# M703X.net
KiCad netlist of a schematic drawn in EAGLE
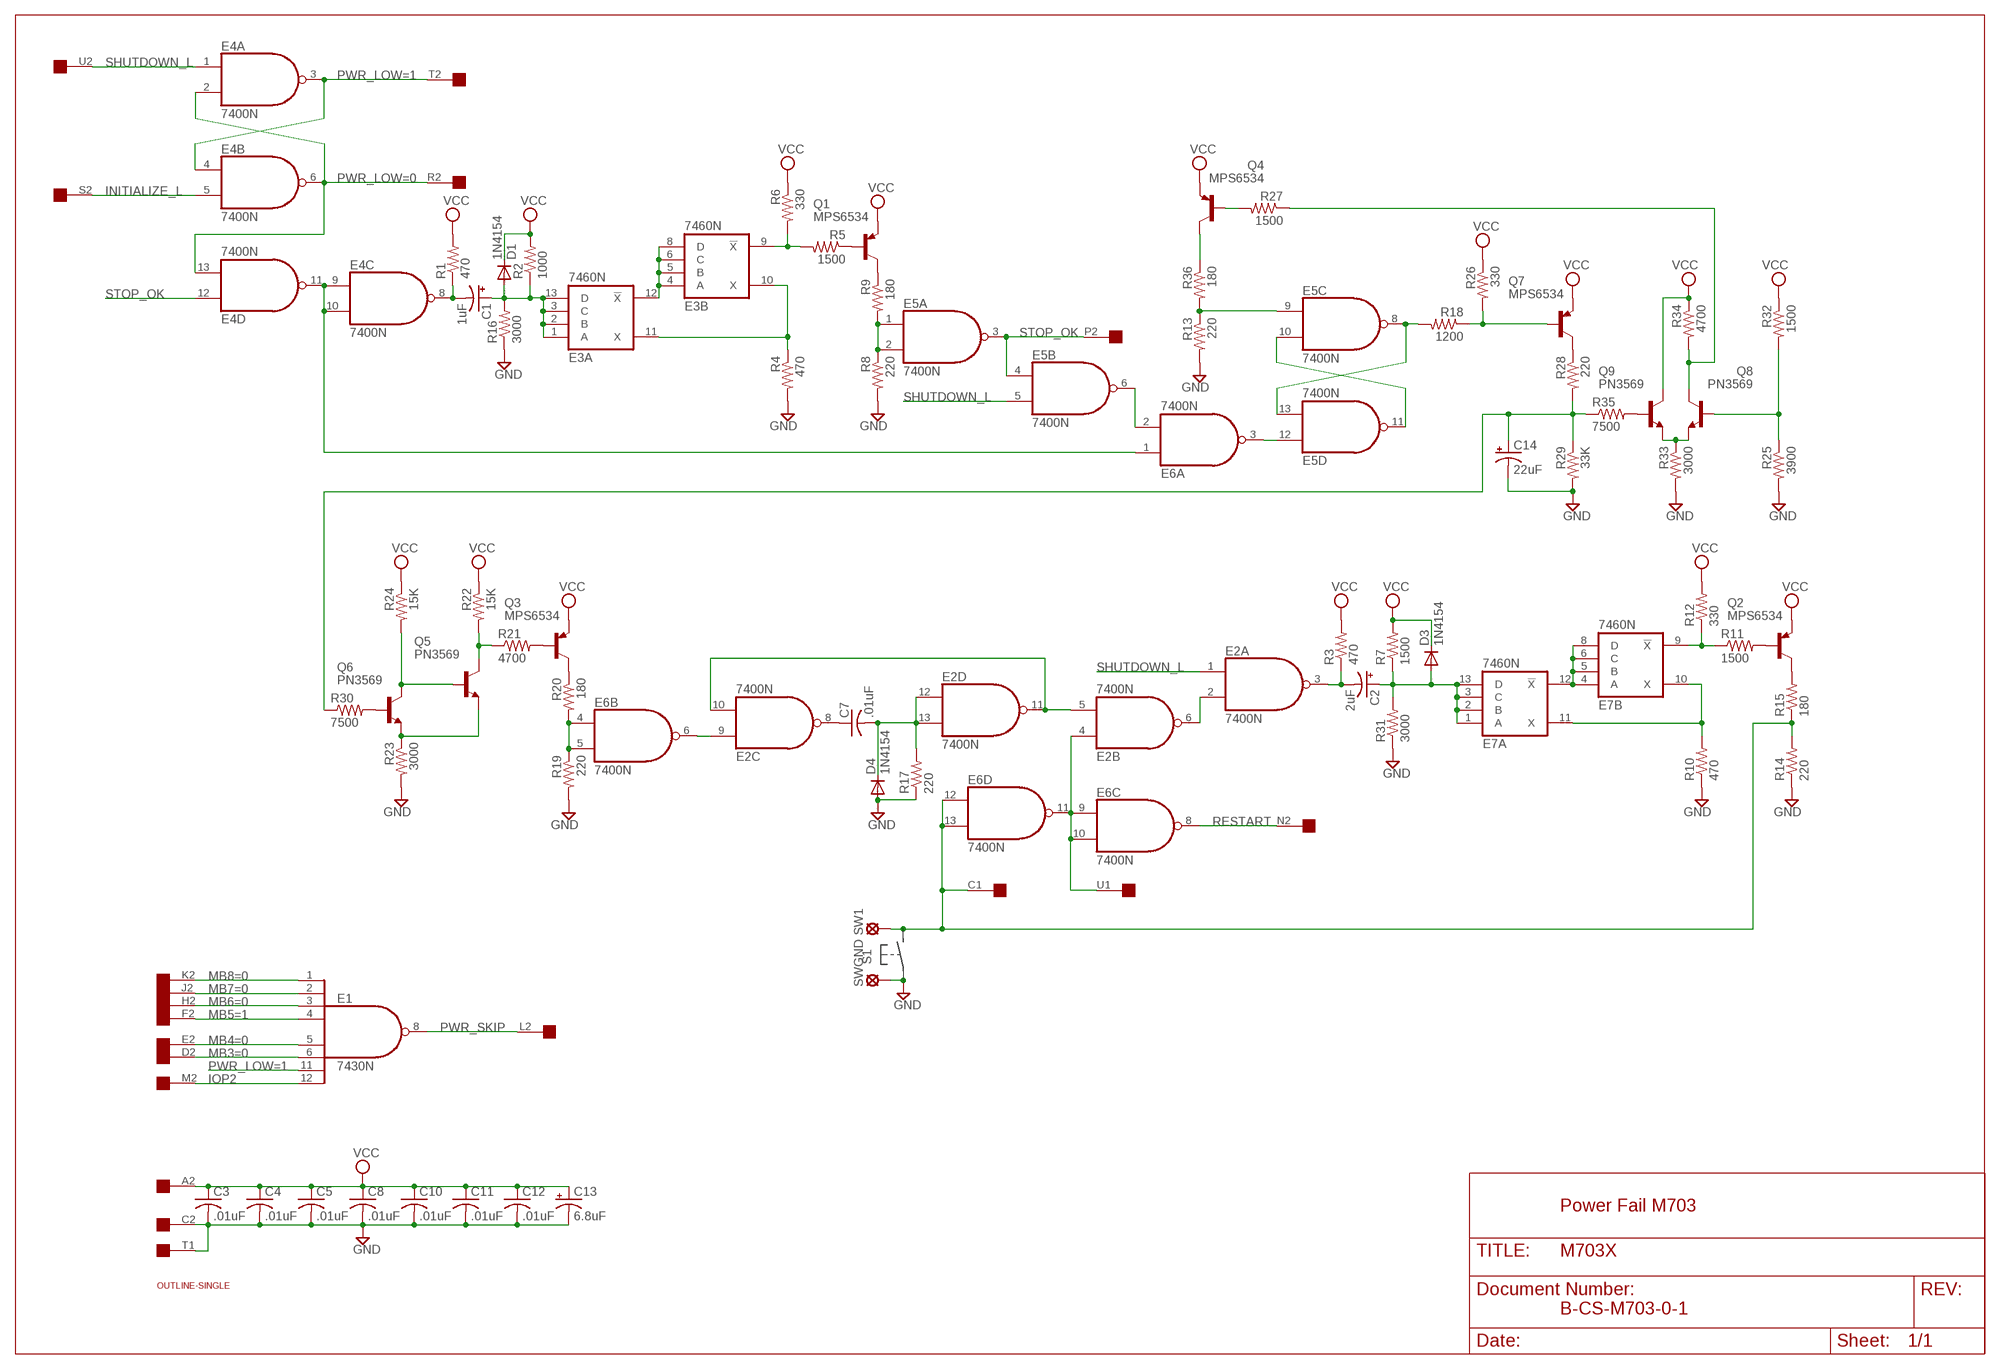
[diagram p0: schematic, sheet 1]

(export (version "E")
  (design (tool "Eeschema 10.0.6"))
  (components
    (comp (ref "C1")
      (value "1uF")
      (footprint "eagle-import:E12-4")
      (libsource (lib "eagle-import") (part "CPOL-USE12-4AXIAL"))
    )
    (comp (ref "C2")
      (value "2uF")
      (footprint "eagle-import:E12-4")
      (libsource (lib "eagle-import") (part "CPOL-USE12-4AXIAL"))
    )
    (comp (ref "C3")
      (value ".01uF")
      (footprint "eagle-import:C050-025X075")
      (libsource (lib "eagle-import") (part "C-US050-025X075"))
    )
    (comp (ref "C4")
      (value ".01uF")
      (footprint "eagle-import:C050-025X075")
      (libsource (lib "eagle-import") (part "C-US050-025X075"))
    )
    (comp (ref "C5")
      (value ".01uF")
      (footprint "eagle-import:C050-025X075")
      (libsource (lib "eagle-import") (part "C-US050-025X075"))
    )
    (comp (ref "C7")
      (value ".01uF")
      (footprint "eagle-import:C050-025X075")
      (libsource (lib "eagle-import") (part "C-US050-025X075"))
    )
    (comp (ref "C8")
      (value ".01uF")
      (footprint "eagle-import:C050-025X075")
      (libsource (lib "eagle-import") (part "C-US050-025X075"))
    )
    (comp (ref "C10")
      (value ".01uF")
      (footprint "eagle-import:C050-025X075")
      (libsource (lib "eagle-import") (part "C-US050-025X075"))
    )
    (comp (ref "C11")
      (value ".01uF")
      (footprint "eagle-import:C050-025X075")
      (libsource (lib "eagle-import") (part "C-US050-025X075"))
    )
    (comp (ref "C12")
      (value ".01uF")
      (footprint "eagle-import:C050-025X075")
      (libsource (lib "eagle-import") (part "C-US050-025X075"))
    )
    (comp (ref "C13")
      (value "6.8uF")
      (footprint "eagle-import:E15-5")
      (libsource (lib "eagle-import") (part "CPOL-USE15-5AXIAL"))
    )
    (comp (ref "C14")
      (value "22uF")
      (footprint "eagle-import:E15-5")
      (libsource (lib "eagle-import") (part "CPOL-USE15-5AXIAL"))
    )
    (comp (ref "D1")
      (value "1N4154")
      (footprint "eagle-import:DO35-10")
      (libsource (lib "eagle-import") (part "1N4148DO35-10"))
    )
    (comp (ref "D3")
      (value "1N4154")
      (footprint "eagle-import:DO35-10")
      (libsource (lib "eagle-import") (part "1N4148DO35-10"))
    )
    (comp (ref "D4")
      (value "1N4154")
      (footprint "eagle-import:DO35-10")
      (libsource (lib "eagle-import") (part "1N4148DO35-10"))
    )
    (comp (ref "E1")
      (value "7430N")
      (footprint "eagle-import:DIL14")
      (libsource (lib "eagle-import") (part "7430N"))
    )
    (comp (ref "E2")
      (value "7400N")
      (footprint "eagle-import:DIL14")
      (libsource (lib "eagle-import") (part "7400N"))
    )
    (comp (ref "E3")
      (value "7460N")
      (footprint "eagle-import:DIL14")
      (libsource (lib "eagle-import") (part "7460N"))
    )
    (comp (ref "E4")
      (value "7400N")
      (footprint "eagle-import:DIL14")
      (libsource (lib "eagle-import") (part "7400N"))
    )
    (comp (ref "E5")
      (value "7400N")
      (footprint "eagle-import:DIL14")
      (libsource (lib "eagle-import") (part "7400N"))
    )
    (comp (ref "E6")
      (value "7400N")
      (footprint "eagle-import:DIL14")
      (libsource (lib "eagle-import") (part "7400N"))
    )
    (comp (ref "E7")
      (value "7460N")
      (footprint "eagle-import:DIL14")
      (libsource (lib "eagle-import") (part "7460N"))
    )
    (comp (ref "Q1")
      (value "MPS6534")
      (footprint "eagle-import:TO39")
      (libsource (lib "eagle-import") (part "2N2904"))
    )
    (comp (ref "Q2")
      (value "MPS6534")
      (footprint "eagle-import:TO39")
      (libsource (lib "eagle-import") (part "2N2904"))
    )
    (comp (ref "Q3")
      (value "MPS6534")
      (footprint "eagle-import:TO39")
      (libsource (lib "eagle-import") (part "2N2904"))
    )
    (comp (ref "Q4")
      (value "MPS6534")
      (footprint "eagle-import:TO39")
      (libsource (lib "eagle-import") (part "2N2904"))
    )
    (comp (ref "Q5")
      (value "PN3569")
      (footprint "eagle-import:TO5")
      (libsource (lib "eagle-import") (part "2N2219"))
    )
    (comp (ref "Q6")
      (value "PN3569")
      (footprint "eagle-import:TO5")
      (libsource (lib "eagle-import") (part "2N2219"))
    )
    (comp (ref "Q7")
      (value "MPS6534")
      (footprint "eagle-import:TO39")
      (libsource (lib "eagle-import") (part "2N2904"))
    )
    (comp (ref "Q8")
      (value "PN3569")
      (footprint "eagle-import:TO5")
      (libsource (lib "eagle-import") (part "2N2219"))
    )
    (comp (ref "Q9")
      (value "PN3569")
      (footprint "eagle-import:TO5")
      (libsource (lib "eagle-import") (part "2N2219"))
    )
    (comp (ref "R1")
      (value "470")
      (footprint "eagle-import:0207_10")
      (libsource (lib "eagle-import") (part "R-US_0207/10"))
    )
    (comp (ref "R2")
      (value "1000")
      (footprint "eagle-import:0207_10")
      (libsource (lib "eagle-import") (part "R-US_0207/10"))
    )
    (comp (ref "R3")
      (value "470")
      (footprint "eagle-import:0207_10")
      (libsource (lib "eagle-import") (part "R-US_0207/10"))
    )
    (comp (ref "R4")
      (value "470")
      (footprint "eagle-import:0207_10")
      (libsource (lib "eagle-import") (part "R-US_0207/10"))
    )
    (comp (ref "R5")
      (value "1500")
      (footprint "eagle-import:0207_10")
      (libsource (lib "eagle-import") (part "R-US_0207/10"))
    )
    (comp (ref "R6")
      (value "330")
      (footprint "eagle-import:0207_10")
      (libsource (lib "eagle-import") (part "R-US_0207/10"))
    )
    (comp (ref "R7")
      (value "1500")
      (footprint "eagle-import:0207_10")
      (libsource (lib "eagle-import") (part "R-US_0207/10"))
    )
    (comp (ref "R8")
      (value "220")
      (footprint "eagle-import:0207_10")
      (libsource (lib "eagle-import") (part "R-US_0207/10"))
    )
    (comp (ref "R9")
      (value "180")
      (footprint "eagle-import:0207_10")
      (libsource (lib "eagle-import") (part "R-US_0207/10"))
    )
    (comp (ref "R10")
      (value "470")
      (footprint "eagle-import:0207_10")
      (libsource (lib "eagle-import") (part "R-US_0207/10"))
    )
    (comp (ref "R11")
      (value "1500")
      (footprint "eagle-import:0207_10")
      (libsource (lib "eagle-import") (part "R-US_0207/10"))
    )
    (comp (ref "R12")
      (value "330")
      (footprint "eagle-import:0207_10")
      (libsource (lib "eagle-import") (part "R-US_0207/10"))
    )
    (comp (ref "R13")
      (value "220")
      (footprint "eagle-import:0207_10")
      (libsource (lib "eagle-import") (part "R-US_0207/10"))
    )
    (comp (ref "R14")
      (value "220")
      (footprint "eagle-import:0207_10")
      (libsource (lib "eagle-import") (part "R-US_0207/10"))
    )
    (comp (ref "R15")
      (value "180")
      (footprint "eagle-import:0207_10")
      (libsource (lib "eagle-import") (part "R-US_0207/10"))
    )
    (comp (ref "R16")
      (value "3000")
      (footprint "eagle-import:0207_10")
      (libsource (lib "eagle-import") (part "R-US_0207/10"))
    )
    (comp (ref "R17")
      (value "220")
      (footprint "eagle-import:0207_10")
      (libsource (lib "eagle-import") (part "R-US_0207/10"))
    )
    (comp (ref "R18")
      (value "1200")
      (footprint "eagle-import:0207_10")
      (libsource (lib "eagle-import") (part "R-US_0207/10"))
    )
    (comp (ref "R19")
      (value "220")
      (footprint "eagle-import:0207_10")
      (libsource (lib "eagle-import") (part "R-US_0207/10"))
    )
    (comp (ref "R20")
      (value "180")
      (footprint "eagle-import:0207_10")
      (libsource (lib "eagle-import") (part "R-US_0207/10"))
    )
    (comp (ref "R21")
      (value "4700")
      (footprint "eagle-import:0207_10")
      (libsource (lib "eagle-import") (part "R-US_0207/10"))
    )
    (comp (ref "R22")
      (value "15K")
      (footprint "eagle-import:0207_10")
      (libsource (lib "eagle-import") (part "R-US_0207/10"))
    )
    (comp (ref "R23")
      (value "3000")
      (footprint "eagle-import:0207_10")
      (libsource (lib "eagle-import") (part "R-US_0207/10"))
    )
    (comp (ref "R24")
      (value "15K")
      (footprint "eagle-import:0207_10")
      (libsource (lib "eagle-import") (part "R-US_0207/10"))
    )
    (comp (ref "R25")
      (value "3900")
      (footprint "eagle-import:0207_10")
      (libsource (lib "eagle-import") (part "R-US_0207/10"))
    )
    (comp (ref "R26")
      (value "330")
      (footprint "eagle-import:0207_10")
      (libsource (lib "eagle-import") (part "R-US_0207/10"))
    )
    (comp (ref "R27")
      (value "1500")
      (footprint "eagle-import:0207_10")
      (libsource (lib "eagle-import") (part "R-US_0207/10"))
    )
    (comp (ref "R28")
      (value "220")
      (footprint "eagle-import:0207_10")
      (libsource (lib "eagle-import") (part "R-US_0207/10"))
    )
    (comp (ref "R29")
      (value "33K")
      (footprint "eagle-import:0207_10")
      (libsource (lib "eagle-import") (part "R-US_0207/10"))
    )
    (comp (ref "R30")
      (value "7500")
      (footprint "eagle-import:0207_10")
      (libsource (lib "eagle-import") (part "R-US_0207/10"))
    )
    (comp (ref "R31")
      (value "3000")
      (footprint "eagle-import:0207_10")
      (libsource (lib "eagle-import") (part "R-US_0207/10"))
    )
    (comp (ref "R32")
      (value "1500")
      (footprint "eagle-import:0207_10")
      (libsource (lib "eagle-import") (part "R-US_0207/10"))
    )
    (comp (ref "R33")
      (value "3000")
      (footprint "eagle-import:0207_10")
      (libsource (lib "eagle-import") (part "R-US_0207/10"))
    )
    (comp (ref "R34")
      (value "4700")
      (footprint "eagle-import:0207_10")
      (libsource (lib "eagle-import") (part "R-US_0207/10"))
    )
    (comp (ref "R35")
      (value "7500")
      (footprint "eagle-import:0207_10")
      (libsource (lib "eagle-import") (part "R-US_0207/10"))
    )
    (comp (ref "R36")
      (value "180")
      (footprint "eagle-import:0207_10")
      (libsource (lib "eagle-import") (part "R-US_0207/10"))
    )
    (comp (ref "SW1")
      (value "SE14")
      (footprint "eagle-import:SE14")
      (libsource (lib "eagle-import") (part "SE14"))
    )
    (comp (ref "SWGND")
      (value "SE14")
      (footprint "eagle-import:SE14")
      (libsource (lib "eagle-import") (part "SE14"))
    )
    (comp (ref "U$2")
      (value "SINGLE")
      (footprint "eagle-import:EDGE-CON2")
      (libsource (lib "eagle-import") (part "SINGLE"))
    )
    (comp (ref "U$4")
      (value "OUTLINE-SINGLE")
      (footprint "eagle-import:SINGLE")
      (libsource (lib "eagle-import") (part "OUTLINE-SINGLE"))
    )
  )
  (nets
    (net (code "1") (name "/INITIALIZE_L") (class "Default")
      (node (ref "E4") (pin "5") (pinfunction "I1_5") (pintype "input"))
      (node (ref "U$2") (pin "S2") (pinfunction "1_S2") (pintype "bidirectional"))
    )
    (net (code "2") (name "/IOP2") (class "Default")
      (node (ref "E1") (pin "12") (pinfunction "I7_12") (pintype "input"))
      (node (ref "U$2") (pin "M2") (pinfunction "1_M2") (pintype "bidirectional"))
    )
    (net (code "3") (name "/MB3=0") (class "Default")
      (node (ref "E1") (pin "6") (pinfunction "I5_6") (pintype "input"))
      (node (ref "U$2") (pin "D2") (pinfunction "1_D2") (pintype "bidirectional"))
    )
    (net (code "4") (name "/MB4=0") (class "Default")
      (node (ref "E1") (pin "5") (pinfunction "I4_5") (pintype "input"))
      (node (ref "U$2") (pin "E2") (pinfunction "1_E2") (pintype "bidirectional"))
    )
    (net (code "5") (name "/MB5=1") (class "Default")
      (node (ref "E1") (pin "4") (pinfunction "I3_4") (pintype "input"))
      (node (ref "U$2") (pin "F2") (pinfunction "1_F2") (pintype "bidirectional"))
    )
    (net (code "6") (name "/MB6=0") (class "Default")
      (node (ref "E1") (pin "3") (pinfunction "I2_3") (pintype "input"))
      (node (ref "U$2") (pin "H2") (pinfunction "1_H2") (pintype "bidirectional"))
    )
    (net (code "7") (name "/MB7=0") (class "Default")
      (node (ref "E1") (pin "2") (pinfunction "I1_2") (pintype "input"))
      (node (ref "U$2") (pin "J2") (pinfunction "1_J2") (pintype "bidirectional"))
    )
    (net (code "8") (name "/MB8=0") (class "Default")
      (node (ref "E1") (pin "1") (pinfunction "I0_1") (pintype "input"))
      (node (ref "U$2") (pin "K2") (pinfunction "1_K2") (pintype "bidirectional"))
    )
    (net (code "9") (name "/PWR_LOW=0") (class "Default")
      (node (ref "E4") (pin "13") (pinfunction "I1_13") (pintype "input"))
      (node (ref "E4") (pin "2") (pinfunction "I1_2") (pintype "input"))
      (node (ref "E4") (pin "6") (pinfunction "O_6") (pintype "output"))
      (node (ref "U$2") (pin "R2") (pinfunction "1_R2") (pintype "bidirectional"))
    )
    (net (code "10") (name "/PWR_LOW=1") (class "Default")
      (node (ref "E1") (pin "11") (pinfunction "I6_11") (pintype "input"))
      (node (ref "E4") (pin "3") (pinfunction "O_3") (pintype "output"))
      (node (ref "E4") (pin "4") (pinfunction "I0_4") (pintype "input"))
      (node (ref "U$2") (pin "T2") (pinfunction "1_T2") (pintype "bidirectional"))
    )
    (net (code "11") (name "/PWR_SKIP") (class "Default")
      (node (ref "E1") (pin "8") (pinfunction "O_8") (pintype "output"))
      (node (ref "U$2") (pin "L2") (pinfunction "1_L2") (pintype "bidirectional"))
    )
    (net (code "12") (name "/RESTART") (class "Default")
      (node (ref "E6") (pin "8") (pinfunction "O_8") (pintype "output"))
      (node (ref "U$2") (pin "N2") (pinfunction "1_N2") (pintype "bidirectional"))
    )
    (net (code "13") (name "/SHUTDOWN_L") (class "Default")
      (node (ref "E2") (pin "1") (pinfunction "I0_1") (pintype "input"))
      (node (ref "E4") (pin "1") (pinfunction "I0_1") (pintype "input"))
      (node (ref "E5") (pin "5") (pinfunction "I1_5") (pintype "input"))
      (node (ref "U$2") (pin "U2") (pinfunction "1_U2") (pintype "bidirectional"))
    )
    (net (code "14") (name "/STOP_OK") (class "Default")
      (node (ref "E4") (pin "12") (pinfunction "I0_12") (pintype "input"))
      (node (ref "E5") (pin "3") (pinfunction "O_3") (pintype "output"))
      (node (ref "E5") (pin "4") (pinfunction "I0_4") (pintype "input"))
      (node (ref "U$2") (pin "P2") (pinfunction "1_P2") (pintype "bidirectional"))
    )
    (net (code "15") (name "GND") (class "Default")
      (node (ref "C10") (pin "2") (pinfunction "2_2") (pintype "passive"))
      (node (ref "C11") (pin "2") (pinfunction "2_2") (pintype "passive"))
      (node (ref "C12") (pin "2") (pinfunction "2_2") (pintype "passive"))
      (node (ref "C13") (pin "-") (pinfunction "-_-") (pintype "passive"))
      (node (ref "C14") (pin "-") (pinfunction "-_-") (pintype "passive"))
      (node (ref "C3") (pin "2") (pinfunction "2_2") (pintype "passive"))
      (node (ref "C4") (pin "2") (pinfunction "2_2") (pintype "passive"))
      (node (ref "C5") (pin "2") (pinfunction "2_2") (pintype "passive"))
      (node (ref "C8") (pin "2") (pinfunction "2_2") (pintype "passive"))
      (node (ref "D4") (pin "A") (pinfunction "A_A") (pintype "passive"))
      (node (ref "R10") (pin "1") (pinfunction "1_1") (pintype "passive"))
      (node (ref "R13") (pin "2") (pinfunction "2_2") (pintype "passive"))
      (node (ref "R14") (pin "1") (pinfunction "1_1") (pintype "passive"))
      (node (ref "R16") (pin "1") (pinfunction "1_1") (pintype "passive"))
      (node (ref "R17") (pin "1") (pinfunction "1_1") (pintype "passive"))
      (node (ref "R19") (pin "2") (pinfunction "2_2") (pintype "passive"))
      (node (ref "R23") (pin "2") (pinfunction "2_2") (pintype "passive"))
      (node (ref "R25") (pin "2") (pinfunction "2_2") (pintype "passive"))
      (node (ref "R29") (pin "2") (pinfunction "2_2") (pintype "passive"))
      (node (ref "R31") (pin "1") (pinfunction "1_1") (pintype "passive"))
      (node (ref "R33") (pin "2") (pinfunction "2_2") (pintype "passive"))
      (node (ref "R4") (pin "2") (pinfunction "2_2") (pintype "passive"))
      (node (ref "R8") (pin "2") (pinfunction "2_2") (pintype "passive"))
      (node (ref "SWGND") (pin "MP") (pinfunction "MP_MP") (pintype "passive"))
      (node (ref "U$2") (pin "C2") (pinfunction "1_C2") (pintype "bidirectional"))
      (node (ref "U$2") (pin "T1") (pinfunction "1_T1") (pintype "bidirectional"))
    )
    (net (code "16") (name "Net-(C14-Pad+)") (class "Default")
      (node (ref "C14") (pin "+") (pinfunction "+_+") (pintype "passive"))
      (node (ref "R28") (pin "2") (pinfunction "2_2") (pintype "passive"))
      (node (ref "R29") (pin "1") (pinfunction "1_1") (pintype "passive"))
      (node (ref "R30") (pin "1") (pinfunction "1_1") (pintype "passive"))
      (node (ref "R35") (pin "1") (pinfunction "1_1") (pintype "passive"))
    )
    (net (code "17") (name "Net-(E2A-I1)") (class "Default")
      (node (ref "E2") (pin "2") (pinfunction "I1_2") (pintype "input"))
      (node (ref "E2") (pin "6") (pinfunction "O_6") (pintype "output"))
    )
    (net (code "18") (name "Net-(E2A-O)") (class "Default")
      (node (ref "C2") (pin "-") (pinfunction "-_-") (pintype "passive"))
      (node (ref "E2") (pin "3") (pinfunction "O_3") (pintype "output"))
      (node (ref "R3") (pin "1") (pinfunction "1_1") (pintype "passive"))
    )
    (net (code "19") (name "Net-(E2B-I0)") (class "Default")
      (node (ref "E2") (pin "4") (pinfunction "I0_4") (pintype "input"))
      (node (ref "E6") (pin "10") (pinfunction "I1_10") (pintype "input"))
      (node (ref "E6") (pin "11") (pinfunction "O_11") (pintype "output"))
      (node (ref "E6") (pin "9") (pinfunction "I0_9") (pintype "input"))
      (node (ref "U$2") (pin "U1") (pinfunction "1_U1") (pintype "bidirectional"))
    )
    (net (code "20") (name "Net-(E2B-I1)") (class "Default")
      (node (ref "E2") (pin "10") (pinfunction "I1_10") (pintype "input"))
      (node (ref "E2") (pin "11") (pinfunction "O_11") (pintype "output"))
      (node (ref "E2") (pin "5") (pinfunction "I1_5") (pintype "input"))
    )
    (net (code "21") (name "Net-(E2C-I0)") (class "Default")
      (node (ref "E2") (pin "9") (pinfunction "I0_9") (pintype "input"))
      (node (ref "E6") (pin "6") (pinfunction "O_6") (pintype "output"))
    )
    (net (code "22") (name "Net-(E2C-O)") (class "Default")
      (node (ref "C7") (pin "1") (pinfunction "1_1") (pintype "passive"))
      (node (ref "E2") (pin "8") (pinfunction "O_8") (pintype "output"))
    )
    (net (code "23") (name "Net-(E2D-I0)") (class "Default")
      (node (ref "C7") (pin "2") (pinfunction "2_2") (pintype "passive"))
      (node (ref "D4") (pin "C") (pinfunction "C_C") (pintype "passive"))
      (node (ref "E2") (pin "12") (pinfunction "I0_12") (pintype "input"))
      (node (ref "E2") (pin "13") (pinfunction "I1_13") (pintype "input"))
      (node (ref "R17") (pin "2") (pinfunction "2_2") (pintype "passive"))
    )
    (net (code "24") (name "Net-(E3A-A)") (class "Default")
      (node (ref "C1") (pin "+") (pinfunction "+_+") (pintype "passive"))
      (node (ref "D1") (pin "A") (pinfunction "A_A") (pintype "passive"))
      (node (ref "E3") (pin "1") (pinfunction "A_1") (pintype "input"))
      (node (ref "E3") (pin "13") (pinfunction "D_13") (pintype "input"))
      (node (ref "E3") (pin "2") (pinfunction "B_2") (pintype "input"))
      (node (ref "E3") (pin "3") (pinfunction "C_3") (pintype "input"))
      (node (ref "R16") (pin "2") (pinfunction "2_2") (pintype "passive"))
      (node (ref "R2") (pin "1") (pinfunction "1_1") (pintype "passive"))
    )
    (net (code "25") (name "Net-(E3A-X)") (class "Default")
      (node (ref "E3") (pin "10") (pinfunction "X_10") (pintype "output"))
      (node (ref "E3") (pin "11") (pinfunction "X_11") (pintype "output"))
      (node (ref "R4") (pin "1") (pinfunction "1_1") (pintype "passive"))
    )
    (net (code "26") (name "Net-(E3A-~{X})") (class "Default")
      (node (ref "E3") (pin "12") (pinfunction "~{X}_12") (pintype "output"))
      (node (ref "E3") (pin "4") (pinfunction "A_4") (pintype "input"))
      (node (ref "E3") (pin "5") (pinfunction "B_5") (pintype "input"))
      (node (ref "E3") (pin "6") (pinfunction "C_6") (pintype "input"))
      (node (ref "E3") (pin "8") (pinfunction "D_8") (pintype "input"))
    )
    (net (code "27") (name "Net-(E3B-~{X})") (class "Default")
      (node (ref "E3") (pin "9") (pinfunction "~{X}_9") (pintype "output"))
      (node (ref "R5") (pin "2") (pinfunction "2_2") (pintype "passive"))
      (node (ref "R6") (pin "2") (pinfunction "2_2") (pintype "passive"))
    )
    (net (code "28") (name "Net-(E4C-I0)") (class "Default")
      (node (ref "E4") (pin "10") (pinfunction "I1_10") (pintype "input"))
      (node (ref "E4") (pin "11") (pinfunction "O_11") (pintype "output"))
      (node (ref "E4") (pin "9") (pinfunction "I0_9") (pintype "input"))
      (node (ref "E6") (pin "1") (pinfunction "I0_1") (pintype "input"))
    )
    (net (code "29") (name "Net-(E4C-O)") (class "Default")
      (node (ref "C1") (pin "-") (pinfunction "-_-") (pintype "passive"))
      (node (ref "E4") (pin "8") (pinfunction "O_8") (pintype "output"))
      (node (ref "R1") (pin "1") (pinfunction "1_1") (pintype "passive"))
    )
    (net (code "30") (name "Net-(E5A-I0)") (class "Default")
      (node (ref "E5") (pin "1") (pinfunction "I0_1") (pintype "input"))
      (node (ref "E5") (pin "2") (pinfunction "I1_2") (pintype "input"))
      (node (ref "R8") (pin "1") (pinfunction "1_1") (pintype "passive"))
      (node (ref "R9") (pin "2") (pinfunction "2_2") (pintype "passive"))
    )
    (net (code "31") (name "Net-(E5B-O)") (class "Default")
      (node (ref "E5") (pin "6") (pinfunction "O_6") (pintype "output"))
      (node (ref "E6") (pin "2") (pinfunction "I1_2") (pintype "input"))
    )
    (net (code "32") (name "Net-(E5C-I0)") (class "Default")
      (node (ref "E5") (pin "9") (pinfunction "I0_9") (pintype "input"))
      (node (ref "R13") (pin "1") (pinfunction "1_1") (pintype "passive"))
      (node (ref "R36") (pin "2") (pinfunction "2_2") (pintype "passive"))
    )
    (net (code "33") (name "Net-(E5C-I1)") (class "Default")
      (node (ref "E5") (pin "10") (pinfunction "I1_10") (pintype "input"))
      (node (ref "E5") (pin "11") (pinfunction "O_11") (pintype "output"))
    )
    (net (code "34") (name "Net-(E5C-O)") (class "Default")
      (node (ref "E5") (pin "13") (pinfunction "I1_13") (pintype "input"))
      (node (ref "E5") (pin "8") (pinfunction "O_8") (pintype "output"))
      (node (ref "R18") (pin "2") (pinfunction "2_2") (pintype "passive"))
    )
    (net (code "35") (name "Net-(E5D-I0)") (class "Default")
      (node (ref "E5") (pin "12") (pinfunction "I0_12") (pintype "input"))
      (node (ref "E6") (pin "3") (pinfunction "O_3") (pintype "output"))
    )
    (net (code "36") (name "Net-(E6B-I0)") (class "Default")
      (node (ref "E6") (pin "4") (pinfunction "I0_4") (pintype "input"))
      (node (ref "E6") (pin "5") (pinfunction "I1_5") (pintype "input"))
      (node (ref "R19") (pin "1") (pinfunction "1_1") (pintype "passive"))
      (node (ref "R20") (pin "2") (pinfunction "2_2") (pintype "passive"))
    )
    (net (code "37") (name "Net-(E6D-I0)") (class "Default")
      (node (ref "E6") (pin "12") (pinfunction "I0_12") (pintype "input"))
      (node (ref "E6") (pin "13") (pinfunction "I1_13") (pintype "input"))
      (node (ref "R14") (pin "2") (pinfunction "2_2") (pintype "passive"))
      (node (ref "R15") (pin "1") (pinfunction "1_1") (pintype "passive"))
      (node (ref "SW1") (pin "MP") (pinfunction "MP_MP") (pintype "passive"))
      (node (ref "U$2") (pin "C1") (pinfunction "1_C1") (pintype "bidirectional"))
    )
    (net (code "38") (name "Net-(E7A-A)") (class "Default")
      (node (ref "C2") (pin "+") (pinfunction "+_+") (pintype "passive"))
      (node (ref "D3") (pin "A") (pinfunction "A_A") (pintype "passive"))
      (node (ref "E7") (pin "1") (pinfunction "A_1") (pintype "input"))
      (node (ref "E7") (pin "13") (pinfunction "D_13") (pintype "input"))
      (node (ref "E7") (pin "2") (pinfunction "B_2") (pintype "input"))
      (node (ref "E7") (pin "3") (pinfunction "C_3") (pintype "input"))
      (node (ref "R31") (pin "2") (pinfunction "2_2") (pintype "passive"))
      (node (ref "R7") (pin "1") (pinfunction "1_1") (pintype "passive"))
    )
    (net (code "39") (name "Net-(E7A-X)") (class "Default")
      (node (ref "E7") (pin "10") (pinfunction "X_10") (pintype "output"))
      (node (ref "E7") (pin "11") (pinfunction "X_11") (pintype "output"))
      (node (ref "R10") (pin "2") (pinfunction "2_2") (pintype "passive"))
    )
    (net (code "40") (name "Net-(E7A-~{X})") (class "Default")
      (node (ref "E7") (pin "12") (pinfunction "~{X}_12") (pintype "output"))
      (node (ref "E7") (pin "4") (pinfunction "A_4") (pintype "input"))
      (node (ref "E7") (pin "5") (pinfunction "B_5") (pintype "input"))
      (node (ref "E7") (pin "6") (pinfunction "C_6") (pintype "input"))
      (node (ref "E7") (pin "8") (pinfunction "D_8") (pintype "input"))
    )
    (net (code "41") (name "Net-(E7B-~{X})") (class "Default")
      (node (ref "E7") (pin "9") (pinfunction "~{X}_9") (pintype "output"))
      (node (ref "R11") (pin "1") (pinfunction "1_1") (pintype "passive"))
      (node (ref "R12") (pin "1") (pinfunction "1_1") (pintype "passive"))
    )
    (net (code "42") (name "Net-(Q1-B)") (class "Default")
      (node (ref "Q1") (pin "2") (pinfunction "B_2") (pintype "passive"))
      (node (ref "R5") (pin "1") (pinfunction "1_1") (pintype "passive"))
    )
    (net (code "43") (name "Net-(Q1-C)") (class "Default")
      (node (ref "Q1") (pin "3") (pinfunction "C_3") (pintype "passive"))
      (node (ref "R9") (pin "1") (pinfunction "1_1") (pintype "passive"))
    )
    (net (code "44") (name "Net-(Q2-B)") (class "Default")
      (node (ref "Q2") (pin "2") (pinfunction "B_2") (pintype "passive"))
      (node (ref "R11") (pin "2") (pinfunction "2_2") (pintype "passive"))
    )
    (net (code "45") (name "Net-(Q2-C)") (class "Default")
      (node (ref "Q2") (pin "3") (pinfunction "C_3") (pintype "passive"))
      (node (ref "R15") (pin "2") (pinfunction "2_2") (pintype "passive"))
    )
    (net (code "46") (name "Net-(Q3-B)") (class "Default")
      (node (ref "Q3") (pin "2") (pinfunction "B_2") (pintype "passive"))
      (node (ref "R21") (pin "2") (pinfunction "2_2") (pintype "passive"))
    )
    (net (code "47") (name "Net-(Q3-C)") (class "Default")
      (node (ref "Q3") (pin "3") (pinfunction "C_3") (pintype "passive"))
      (node (ref "R20") (pin "1") (pinfunction "1_1") (pintype "passive"))
    )
    (net (code "48") (name "Net-(Q4-B)") (class "Default")
      (node (ref "Q4") (pin "2") (pinfunction "B_2") (pintype "passive"))
      (node (ref "R27") (pin "2") (pinfunction "2_2") (pintype "passive"))
    )
    (net (code "49") (name "Net-(Q4-C)") (class "Default")
      (node (ref "Q4") (pin "3") (pinfunction "C_3") (pintype "passive"))
      (node (ref "R36") (pin "1") (pinfunction "1_1") (pintype "passive"))
    )
    (net (code "50") (name "Net-(Q5-B)") (class "Default")
      (node (ref "Q5") (pin "2") (pinfunction "B_2") (pintype "passive"))
      (node (ref "Q6") (pin "3") (pinfunction "C_3") (pintype "passive"))
      (node (ref "R24") (pin "2") (pinfunction "2_2") (pintype "passive"))
    )
    (net (code "51") (name "Net-(Q5-C)") (class "Default")
      (node (ref "Q5") (pin "3") (pinfunction "C_3") (pintype "passive"))
      (node (ref "R21") (pin "1") (pinfunction "1_1") (pintype "passive"))
      (node (ref "R22") (pin "2") (pinfunction "2_2") (pintype "passive"))
    )
    (net (code "52") (name "Net-(Q5-E)") (class "Default")
      (node (ref "Q5") (pin "1") (pinfunction "E_1") (pintype "passive"))
      (node (ref "Q6") (pin "1") (pinfunction "E_1") (pintype "passive"))
      (node (ref "R23") (pin "1") (pinfunction "1_1") (pintype "passive"))
    )
    (net (code "53") (name "Net-(Q6-B)") (class "Default")
      (node (ref "Q6") (pin "2") (pinfunction "B_2") (pintype "passive"))
      (node (ref "R30") (pin "2") (pinfunction "2_2") (pintype "passive"))
    )
    (net (code "54") (name "Net-(Q7-B)") (class "Default")
      (node (ref "Q7") (pin "2") (pinfunction "B_2") (pintype "passive"))
      (node (ref "R18") (pin "1") (pinfunction "1_1") (pintype "passive"))
      (node (ref "R26") (pin "2") (pinfunction "2_2") (pintype "passive"))
    )
    (net (code "55") (name "Net-(Q7-C)") (class "Default")
      (node (ref "Q7") (pin "3") (pinfunction "C_3") (pintype "passive"))
      (node (ref "R28") (pin "1") (pinfunction "1_1") (pintype "passive"))
    )
    (net (code "56") (name "Net-(Q8-B)") (class "Default")
      (node (ref "Q8") (pin "2") (pinfunction "B_2") (pintype "passive"))
      (node (ref "R25") (pin "1") (pinfunction "1_1") (pintype "passive"))
      (node (ref "R32") (pin "2") (pinfunction "2_2") (pintype "passive"))
    )
    (net (code "57") (name "Net-(Q8-C)") (class "Default")
      (node (ref "Q8") (pin "3") (pinfunction "C_3") (pintype "passive"))
      (node (ref "R27") (pin "1") (pinfunction "1_1") (pintype "passive"))
      (node (ref "R34") (pin "2") (pinfunction "2_2") (pintype "passive"))
    )
    (net (code "58") (name "Net-(Q8-E)") (class "Default")
      (node (ref "Q8") (pin "1") (pinfunction "E_1") (pintype "passive"))
      (node (ref "Q9") (pin "1") (pinfunction "E_1") (pintype "passive"))
      (node (ref "R33") (pin "1") (pinfunction "1_1") (pintype "passive"))
    )
    (net (code "59") (name "Net-(Q9-B)") (class "Default")
      (node (ref "Q9") (pin "2") (pinfunction "B_2") (pintype "passive"))
      (node (ref "R35") (pin "2") (pinfunction "2_2") (pintype "passive"))
    )
    (net (code "60") (name "VCC") (class "Default")
      (node (ref "C10") (pin "1") (pinfunction "1_1") (pintype "passive"))
      (node (ref "C11") (pin "1") (pinfunction "1_1") (pintype "passive"))
      (node (ref "C12") (pin "1") (pinfunction "1_1") (pintype "passive"))
      (node (ref "C13") (pin "+") (pinfunction "+_+") (pintype "passive"))
      (node (ref "C3") (pin "1") (pinfunction "1_1") (pintype "passive"))
      (node (ref "C4") (pin "1") (pinfunction "1_1") (pintype "passive"))
      (node (ref "C5") (pin "1") (pinfunction "1_1") (pintype "passive"))
      (node (ref "C8") (pin "1") (pinfunction "1_1") (pintype "passive"))
      (node (ref "D1") (pin "C") (pinfunction "C_C") (pintype "passive"))
      (node (ref "D3") (pin "C") (pinfunction "C_C") (pintype "passive"))
      (node (ref "Q1") (pin "1") (pinfunction "E_1") (pintype "passive"))
      (node (ref "Q2") (pin "1") (pinfunction "E_1") (pintype "passive"))
      (node (ref "Q3") (pin "1") (pinfunction "E_1") (pintype "passive"))
      (node (ref "Q4") (pin "1") (pinfunction "E_1") (pintype "passive"))
      (node (ref "Q7") (pin "1") (pinfunction "E_1") (pintype "passive"))
      (node (ref "Q9") (pin "3") (pinfunction "C_3") (pintype "passive"))
      (node (ref "R1") (pin "2") (pinfunction "2_2") (pintype "passive"))
      (node (ref "R12") (pin "2") (pinfunction "2_2") (pintype "passive"))
      (node (ref "R2") (pin "2") (pinfunction "2_2") (pintype "passive"))
      (node (ref "R22") (pin "1") (pinfunction "1_1") (pintype "passive"))
      (node (ref "R24") (pin "1") (pinfunction "1_1") (pintype "passive"))
      (node (ref "R26") (pin "1") (pinfunction "1_1") (pintype "passive"))
      (node (ref "R3") (pin "2") (pinfunction "2_2") (pintype "passive"))
      (node (ref "R32") (pin "1") (pinfunction "1_1") (pintype "passive"))
      (node (ref "R34") (pin "1") (pinfunction "1_1") (pintype "passive"))
      (node (ref "R6") (pin "1") (pinfunction "1_1") (pintype "passive"))
      (node (ref "R7") (pin "2") (pinfunction "2_2") (pintype "passive"))
      (node (ref "U$2") (pin "A2") (pinfunction "1_A2") (pintype "bidirectional"))
    )
  )
)
